# Adafruit_nRF52840_Bluefruit_Feather_Expr.net
KiCad netlist of a schematic drawn in EAGLE
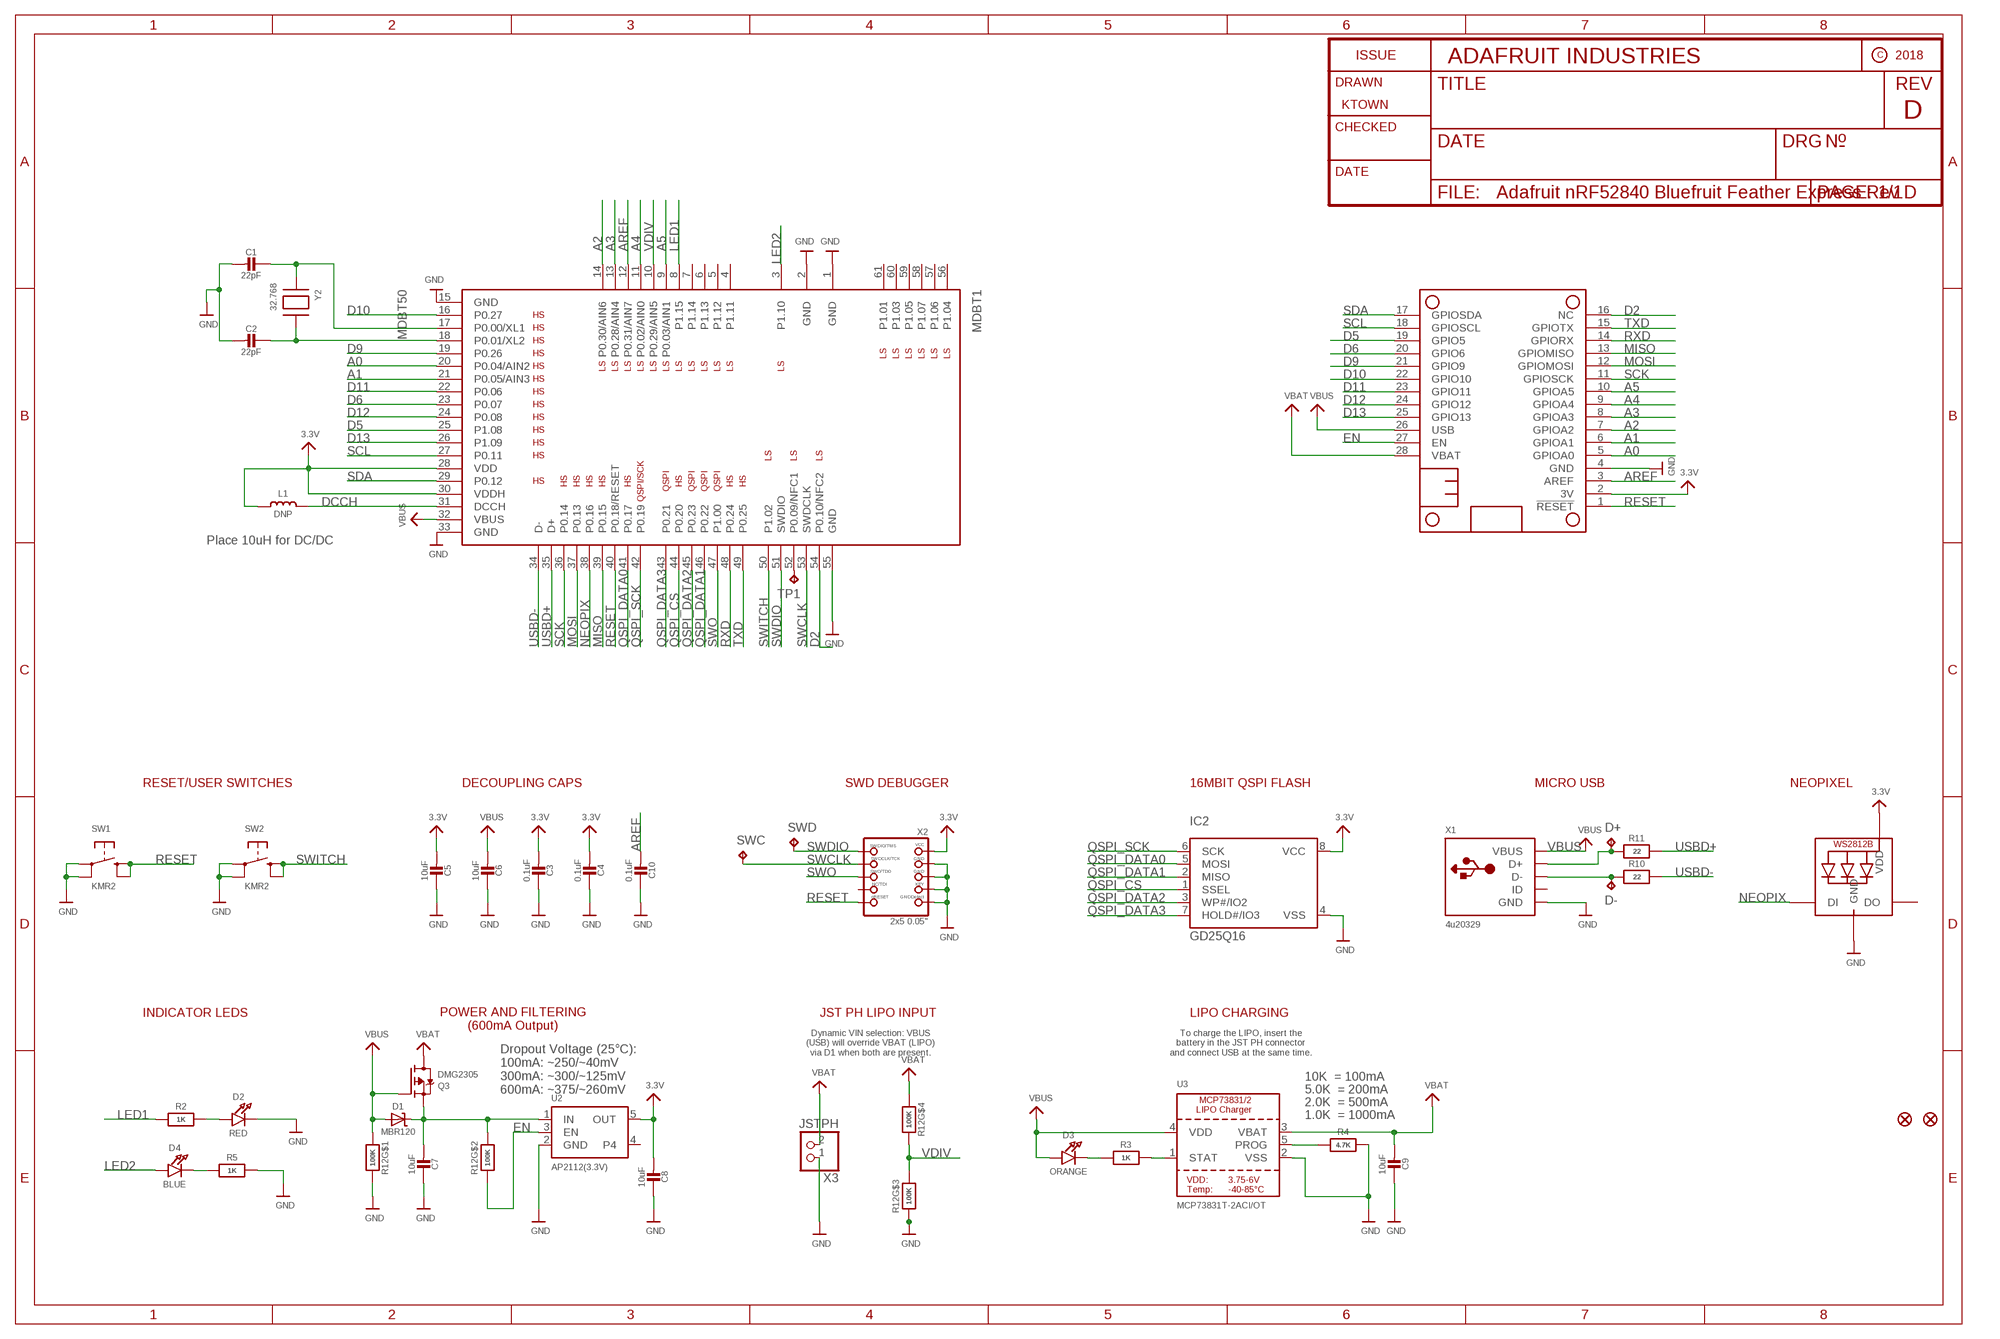
[diagram p0: schematic, sheet 1]

(export (version "E")
  (design (tool "Eeschema 10.0.6"))
  (components
    (comp (ref "C1")
      (value "22pF")
      (footprint "eagle-import:0603-NO")
      (libsource (lib "eagle-import") (part "CAP_CERAMIC0603_NO"))
    )
    (comp (ref "C2")
      (value "22pF")
      (footprint "eagle-import:0603-NO")
      (libsource (lib "eagle-import") (part "CAP_CERAMIC0603_NO"))
    )
    (comp (ref "C3")
      (value "0.1uF")
      (footprint "eagle-import:0603-NO")
      (libsource (lib "eagle-import") (part "CAP_CERAMIC0603_NO"))
    )
    (comp (ref "C4")
      (value "0.1uF")
      (footprint "eagle-import:0603-NO")
      (libsource (lib "eagle-import") (part "CAP_CERAMIC0603_NO"))
    )
    (comp (ref "C5")
      (value "10uF")
      (footprint "eagle-import:0805-NO")
      (libsource (lib "eagle-import") (part "CAP_CERAMIC0805-NOOUTLINE"))
    )
    (comp (ref "C6")
      (value "10uF")
      (footprint "eagle-import:0805-NO")
      (libsource (lib "eagle-import") (part "CAP_CERAMIC0805-NOOUTLINE"))
    )
    (comp (ref "C7")
      (value "10uF")
      (footprint "eagle-import:0805-NO")
      (libsource (lib "eagle-import") (part "CAP_CERAMIC0805-NOOUTLINE"))
    )
    (comp (ref "C8")
      (value "10uF")
      (footprint "eagle-import:0805-NO")
      (libsource (lib "eagle-import") (part "CAP_CERAMIC0805-NOOUTLINE"))
    )
    (comp (ref "C9")
      (value "10uF")
      (footprint "eagle-import:0805-NO")
      (libsource (lib "eagle-import") (part "CAP_CERAMIC0805-NOOUTLINE"))
    )
    (comp (ref "C10")
      (value "0.1uF")
      (footprint "eagle-import:0603-NO")
      (libsource (lib "eagle-import") (part "CAP_CERAMIC0603_NO"))
    )
    (comp (ref "D+")
      (value "TPTP10R")
      (footprint "eagle-import:TP10R")
      (libsource (lib "eagle-import") (part "TPTP10R"))
    )
    (comp (ref "D-")
      (value "TPTP10R")
      (footprint "eagle-import:TP10R")
      (libsource (lib "eagle-import") (part "TPTP10R"))
    )
    (comp (ref "D1")
      (value "MBR120")
      (footprint "eagle-import:SOD-123")
      (libsource (lib "eagle-import") (part "DIODE-SCHOTTKYSOD-123"))
    )
    (comp (ref "D2")
      (value "RED")
      (footprint "eagle-import:CHIPLED_0805_NOOUTLINE")
      (libsource (lib "eagle-import") (part "LED0805_NOOUTLINE"))
    )
    (comp (ref "D3")
      (value "ORANGE")
      (footprint "eagle-import:CHIPLED_0805_NOOUTLINE")
      (libsource (lib "eagle-import") (part "LED0805_NOOUTLINE"))
    )
    (comp (ref "D4")
      (value "BLUE")
      (footprint "eagle-import:CHIPLED_0805_NOOUTLINE")
      (libsource (lib "eagle-import") (part "LED0805_NOOUTLINE"))
    )
    (comp (ref "FID1")
      (value "FIDUCIAL_1MM")
      (footprint "eagle-import:FIDUCIAL_1MM")
      (libsource (lib "eagle-import") (part "FIDUCIAL_1MM"))
    )
    (comp (ref "FID2")
      (value "FIDUCIAL_1MM")
      (footprint "eagle-import:FIDUCIAL_1MM")
      (libsource (lib "eagle-import") (part "FIDUCIAL_1MM"))
    )
    (comp (ref "IC2")
      (value "GD25Q16")
      (footprint "eagle-import:USON8")
      (libsource (lib "eagle-import") (part "SPIFLASH_8PINUX"))
    )
    (comp (ref "L1")
      (value "DNP")
      (footprint "eagle-import:_0805MP")
      (libsource (lib "eagle-import") (part "INDUCTOR_0805MP"))
    )
    (comp (ref "LED1")
      (value "WS2812B3535")
      (footprint "eagle-import:LED3535")
      (libsource (lib "eagle-import") (part "WS2812B3535"))
    )
    (comp (ref "MDBT1")
      (value "MDBT50")
      (footprint "eagle-import:MDBT50")
      (libsource (lib "eagle-import") (part "MDBT50"))
    )
    (comp (ref "MS1")
      (value "FEATHERWING_NODIM")
      (footprint "eagle-import:FEATHERWING_NODIM")
      (libsource (lib "eagle-import") (part "FEATHERWING_NODIM"))
    )
    (comp (ref "Q3")
      (value "DMG2305")
      (footprint "eagle-import:SOT23-R")
      (libsource (lib "eagle-import") (part "MOSFET-P"))
    )
    (comp (ref "R2")
      (value "1K")
      (footprint "eagle-import:0603-NO")
      (libsource (lib "eagle-import") (part "RESISTOR_0603_NOOUT"))
    )
    (comp (ref "R3")
      (value "1K")
      (footprint "eagle-import:0603-NO")
      (libsource (lib "eagle-import") (part "RESISTOR_0603_NOOUT"))
    )
    (comp (ref "R4")
      (value "4.7K")
      (footprint "eagle-import:0603-NO")
      (libsource (lib "eagle-import") (part "RESISTOR_0603_NOOUT"))
    )
    (comp (ref "R5")
      (value "1K")
      (footprint "eagle-import:0603-NO")
      (libsource (lib "eagle-import") (part "RESISTOR_0603_NOOUT"))
    )
    (comp (ref "R10")
      (value "22")
      (footprint "eagle-import:0603-NO")
      (libsource (lib "eagle-import") (part "RESISTOR_0603_NOOUT"))
    )
    (comp (ref "R11")
      (value "22")
      (footprint "eagle-import:0603-NO")
      (libsource (lib "eagle-import") (part "RESISTOR_0603_NOOUT"))
    )
    (comp (ref "R12")
      (value "100K")
      (footprint "eagle-import:RESPACK_4X0603")
      (libsource (lib "eagle-import") (part "RESISTOR_4PACK"))
    )
    (comp (ref "SW1")
      (value "KMR2")
      (footprint "eagle-import:BTN_KMR2_4.6X2.8")
      (libsource (lib "eagle-import") (part "SWITCH_TACT_SMT4.6X2.8"))
    )
    (comp (ref "SW2")
      (value "KMR2")
      (footprint "eagle-import:BTN_KMR2_4.6X2.8")
      (libsource (lib "eagle-import") (part "SWITCH_TACT_SMT4.6X2.8"))
    )
    (comp (ref "SWC")
      (value "TPTP12R")
      (footprint "eagle-import:TP12R")
      (libsource (lib "eagle-import") (part "TPTP12R"))
    )
    (comp (ref "SWD")
      (value "TPTP12R")
      (footprint "eagle-import:TP12R")
      (libsource (lib "eagle-import") (part "TPTP12R"))
    )
    (comp (ref "TP1")
      (value "TPTP10R")
      (footprint "eagle-import:TP10R")
      (libsource (lib "eagle-import") (part "TPTP10R"))
    )
    (comp (ref "U2")
      (value "AP2112(3.3V)")
      (footprint "eagle-import:SOT23-5")
      (libsource (lib "eagle-import") (part "VREG_SOT23-5"))
    )
    (comp (ref "U3")
      (value "MCP73831T-2ACI/OT")
      (footprint "eagle-import:SOT23-5")
      (libsource (lib "eagle-import") (part "MCP73831/2"))
    )
    (comp (ref "X1")
      (value "4u20329")
      (footprint "eagle-import:4UCONN_20329_V2")
      (libsource (lib "eagle-import") (part "USB_MICRO_20329_V2"))
    )
    (comp (ref "X2")
      (value "2x5 0.05\"")
      (footprint "eagle-import:2X05_1.27MM_BOX_POSTS")
      (libsource (lib "eagle-import") (part "JTAG-CORTEXBOXPOSTS"))
    )
    (comp (ref "X3")
      (value "JSTPH")
      (footprint "eagle-import:JSTPH2")
      (libsource (lib "eagle-import") (part "CON_JST_PH_2PIN"))
    )
    (comp (ref "Y2")
      (value "32.768")
      (footprint "eagle-import:XTAL3215")
      (libsource (lib "eagle-import") (part "XTAL-3.2X1.5"))
    )
  )
  (nets
    (net (code "1") (name "/A0") (class "Default")
      (node (ref "MDBT1") (pin "20") (pinfunction "P0.04/AIN2_20") (pintype "bidirectional"))
      (node (ref "MS1") (pin "5") (pinfunction "GPIOA0_5") (pintype "bidirectional"))
    )
    (net (code "2") (name "/A1") (class "Default")
      (node (ref "MDBT1") (pin "21") (pinfunction "P0.05/AIN3_21") (pintype "bidirectional"))
      (node (ref "MS1") (pin "6") (pinfunction "GPIOA1_6") (pintype "bidirectional"))
    )
    (net (code "3") (name "/A2") (class "Default")
      (node (ref "MDBT1") (pin "14") (pinfunction "P0.30/AIN6_14") (pintype "bidirectional"))
      (node (ref "MS1") (pin "7") (pinfunction "GPIOA2_7") (pintype "bidirectional"))
    )
    (net (code "4") (name "/A3") (class "Default")
      (node (ref "MDBT1") (pin "13") (pinfunction "P0.28/AIN4_13") (pintype "bidirectional"))
      (node (ref "MS1") (pin "8") (pinfunction "GPIOA3_8") (pintype "bidirectional"))
    )
    (net (code "5") (name "/A4") (class "Default")
      (node (ref "MDBT1") (pin "11") (pinfunction "P0.02/AIN0_11") (pintype "bidirectional"))
      (node (ref "MS1") (pin "9") (pinfunction "GPIOA4_9") (pintype "bidirectional"))
    )
    (net (code "6") (name "/A5") (class "Default")
      (node (ref "MDBT1") (pin "9") (pinfunction "P0.03/AIN1_9") (pintype "bidirectional"))
      (node (ref "MS1") (pin "10") (pinfunction "GPIOA5_10") (pintype "bidirectional"))
    )
    (net (code "7") (name "/AREF") (class "Default")
      (node (ref "C10") (pin "2") (pinfunction "2_2") (pintype "passive"))
      (node (ref "MDBT1") (pin "12") (pinfunction "P0.31/AIN7_12") (pintype "bidirectional"))
      (node (ref "MS1") (pin "3") (pinfunction "AREF_3") (pintype "passive"))
    )
    (net (code "8") (name "/D2") (class "Default")
      (node (ref "MDBT1") (pin "54") (pinfunction "P0.10/NFC2_54") (pintype "bidirectional"))
      (node (ref "MS1") (pin "16") (pinfunction "NC_16") (pintype "passive"))
    )
    (net (code "9") (name "/D5") (class "Default")
      (node (ref "MDBT1") (pin "25") (pinfunction "P1.08_25") (pintype "bidirectional"))
      (node (ref "MS1") (pin "19") (pinfunction "GPIO5_19") (pintype "bidirectional"))
    )
    (net (code "10") (name "/D6") (class "Default")
      (node (ref "MDBT1") (pin "23") (pinfunction "P0.07_23") (pintype "bidirectional"))
      (node (ref "MS1") (pin "20") (pinfunction "GPIO6_20") (pintype "bidirectional"))
    )
    (net (code "11") (name "/D9") (class "Default")
      (node (ref "MDBT1") (pin "19") (pinfunction "P0.26_19") (pintype "bidirectional"))
      (node (ref "MS1") (pin "21") (pinfunction "GPIO9_21") (pintype "bidirectional"))
    )
    (net (code "12") (name "/D10") (class "Default")
      (node (ref "MDBT1") (pin "16") (pinfunction "P0.27_16") (pintype "bidirectional"))
      (node (ref "MS1") (pin "22") (pinfunction "GPIO10_22") (pintype "bidirectional"))
    )
    (net (code "13") (name "/D11") (class "Default")
      (node (ref "MDBT1") (pin "22") (pinfunction "P0.06_22") (pintype "bidirectional"))
      (node (ref "MS1") (pin "23") (pinfunction "GPIO11_23") (pintype "bidirectional"))
    )
    (net (code "14") (name "/D12") (class "Default")
      (node (ref "MDBT1") (pin "24") (pinfunction "P0.08_24") (pintype "bidirectional"))
      (node (ref "MS1") (pin "24") (pinfunction "GPIO12_24") (pintype "bidirectional"))
    )
    (net (code "15") (name "/D13") (class "Default")
      (node (ref "MDBT1") (pin "26") (pinfunction "P1.09_26") (pintype "bidirectional"))
      (node (ref "MS1") (pin "25") (pinfunction "GPIO13_25") (pintype "bidirectional"))
    )
    (net (code "16") (name "/DCCH") (class "Default")
      (node (ref "L1") (pin "2") (pinfunction "2_2") (pintype "passive"))
      (node (ref "MDBT1") (pin "31") (pinfunction "DCCH_31") (pintype "bidirectional"))
    )
    (net (code "17") (name "/EN") (class "Default")
      (node (ref "MS1") (pin "27") (pinfunction "EN_27") (pintype "passive"))
      (node (ref "R12") (pin "2") (pinfunction "1_2") (pintype "passive"))
      (node (ref "U2") (pin "3") (pinfunction "EN_3") (pintype "input"))
    )
    (net (code "18") (name "/LED1") (class "Default")
      (node (ref "MDBT1") (pin "8") (pinfunction "P1.15_8") (pintype "bidirectional"))
      (node (ref "R2") (pin "1") (pinfunction "1_1") (pintype "passive"))
    )
    (net (code "19") (name "/LED2") (class "Default")
      (node (ref "D4") (pin "A") (pinfunction "A_A") (pintype "passive"))
      (node (ref "MDBT1") (pin "3") (pinfunction "P1.10_3") (pintype "bidirectional"))
    )
    (net (code "20") (name "/MISO") (class "Default")
      (node (ref "MDBT1") (pin "39") (pinfunction "P0.15_39") (pintype "bidirectional"))
      (node (ref "MS1") (pin "13") (pinfunction "GPIOMISO_13") (pintype "bidirectional"))
    )
    (net (code "21") (name "/MOSI") (class "Default")
      (node (ref "MDBT1") (pin "37") (pinfunction "P0.13_37") (pintype "bidirectional"))
      (node (ref "MS1") (pin "12") (pinfunction "GPIOMOSI_12") (pintype "bidirectional"))
    )
    (net (code "22") (name "/NEOPIX") (class "Default")
      (node (ref "LED1") (pin "1") (pinfunction "DI_1") (pintype "input"))
      (node (ref "MDBT1") (pin "38") (pinfunction "P0.16_38") (pintype "bidirectional"))
    )
    (net (code "23") (name "/QSPI_CS") (class "Default")
      (node (ref "IC2") (pin "1") (pinfunction "SSEL_1") (pintype "bidirectional"))
      (node (ref "MDBT1") (pin "44") (pinfunction "P0.20_44") (pintype "bidirectional"))
    )
    (net (code "24") (name "/QSPI_DATA0") (class "Default")
      (node (ref "IC2") (pin "5") (pinfunction "MOSI_5") (pintype "bidirectional"))
      (node (ref "MDBT1") (pin "41") (pinfunction "P0.17_41") (pintype "bidirectional"))
    )
    (net (code "25") (name "/QSPI_DATA1") (class "Default")
      (node (ref "IC2") (pin "2") (pinfunction "MISO_2") (pintype "bidirectional"))
      (node (ref "MDBT1") (pin "46") (pinfunction "P0.22_46") (pintype "bidirectional"))
    )
    (net (code "26") (name "/QSPI_DATA2") (class "Default")
      (node (ref "IC2") (pin "3") (pinfunction "WP#/IO2_3") (pintype "bidirectional"))
      (node (ref "MDBT1") (pin "45") (pinfunction "P0.23_45") (pintype "bidirectional"))
    )
    (net (code "27") (name "/QSPI_DATA3") (class "Default")
      (node (ref "IC2") (pin "7") (pinfunction "HOLD#/IO3_7") (pintype "bidirectional"))
      (node (ref "MDBT1") (pin "43") (pinfunction "P0.21_43") (pintype "bidirectional"))
    )
    (net (code "28") (name "/QSPI_SCK") (class "Default")
      (node (ref "IC2") (pin "6") (pinfunction "SCK_6") (pintype "bidirectional"))
      (node (ref "MDBT1") (pin "42") (pinfunction "P0.19_42") (pintype "bidirectional"))
    )
    (net (code "29") (name "/RESET") (class "Default")
      (node (ref "MDBT1") (pin "40") (pinfunction "P0.18/RESET_40") (pintype "bidirectional"))
      (node (ref "MS1") (pin "1") (pinfunction "~{RESET}_1") (pintype "input"))
      (node (ref "SW1") (pin "B") (pinfunction "S_B") (pintype "passive"))
      (node (ref "SW1") (pin "B'") (pinfunction "S1_B'") (pintype "passive"))
      (node (ref "X2") (pin "10") (pinfunction "NRESET_10") (pintype "bidirectional"))
    )
    (net (code "30") (name "/RXD") (class "Default")
      (node (ref "MDBT1") (pin "48") (pinfunction "P0.24_48") (pintype "bidirectional"))
      (node (ref "MS1") (pin "14") (pinfunction "GPIORX_14") (pintype "bidirectional"))
    )
    (net (code "31") (name "/SCK") (class "Default")
      (node (ref "MDBT1") (pin "36") (pinfunction "P0.14_36") (pintype "bidirectional"))
      (node (ref "MS1") (pin "11") (pinfunction "GPIOSCK_11") (pintype "bidirectional"))
    )
    (net (code "32") (name "/SCL") (class "Default")
      (node (ref "MDBT1") (pin "27") (pinfunction "P0.11_27") (pintype "bidirectional"))
      (node (ref "MS1") (pin "18") (pinfunction "GPIOSCL_18") (pintype "bidirectional"))
    )
    (net (code "33") (name "/SDA") (class "Default")
      (node (ref "MDBT1") (pin "29") (pinfunction "P0.12_29") (pintype "bidirectional"))
      (node (ref "MS1") (pin "17") (pinfunction "GPIOSDA_17") (pintype "bidirectional"))
    )
    (net (code "34") (name "/SWCLK") (class "Default")
      (node (ref "MDBT1") (pin "53") (pinfunction "SWDCLK_53") (pintype "bidirectional"))
      (node (ref "SWC") (pin "TP") (pinfunction "TP_TP") (pintype "input"))
      (node (ref "X2") (pin "4") (pinfunction "SWDCLK_4") (pintype "bidirectional"))
    )
    (net (code "35") (name "/SWDIO") (class "Default")
      (node (ref "MDBT1") (pin "51") (pinfunction "SWDIO_51") (pintype "bidirectional"))
      (node (ref "SWD") (pin "TP") (pinfunction "TP_TP") (pintype "input"))
      (node (ref "X2") (pin "2") (pinfunction "SWDIO_2") (pintype "bidirectional"))
    )
    (net (code "36") (name "/SWITCH") (class "Default")
      (node (ref "MDBT1") (pin "50") (pinfunction "P1.02_50") (pintype "bidirectional"))
      (node (ref "SW2") (pin "B") (pinfunction "S_B") (pintype "passive"))
      (node (ref "SW2") (pin "B'") (pinfunction "S1_B'") (pintype "passive"))
    )
    (net (code "37") (name "/SWO") (class "Default")
      (node (ref "MDBT1") (pin "47") (pinfunction "P1.00_47") (pintype "bidirectional"))
      (node (ref "X2") (pin "6") (pinfunction "SWO_6") (pintype "bidirectional"))
    )
    (net (code "38") (name "/TXD") (class "Default")
      (node (ref "MDBT1") (pin "49") (pinfunction "P0.25_49") (pintype "bidirectional"))
      (node (ref "MS1") (pin "15") (pinfunction "GPIOTX_15") (pintype "bidirectional"))
    )
    (net (code "39") (name "/USBD+") (class "Default")
      (node (ref "MDBT1") (pin "35") (pinfunction "D+_35") (pintype "bidirectional"))
      (node (ref "R11") (pin "2") (pinfunction "2_2") (pintype "passive"))
    )
    (net (code "40") (name "/USBD-") (class "Default")
      (node (ref "MDBT1") (pin "34") (pinfunction "D-_34") (pintype "bidirectional"))
      (node (ref "R10") (pin "2") (pinfunction "2_2") (pintype "passive"))
    )
    (net (code "41") (name "/VDIV") (class "Default")
      (node (ref "MDBT1") (pin "10") (pinfunction "P0.29/AIN5_10") (pintype "bidirectional"))
      (node (ref "R12") (pin "5") (pinfunction "2_5") (pintype "passive"))
      (node (ref "R12") (pin "6") (pinfunction "2_6") (pintype "passive"))
    )
    (net (code "42") (name "3.3V") (class "Default")
      (node (ref "C3") (pin "2") (pinfunction "2_2") (pintype "passive"))
      (node (ref "C4") (pin "2") (pinfunction "2_2") (pintype "passive"))
      (node (ref "C5") (pin "2") (pinfunction "2_2") (pintype "passive"))
      (node (ref "C8") (pin "2") (pinfunction "2_2") (pintype "passive"))
      (node (ref "IC2") (pin "8") (pinfunction "VCC_8") (pintype "bidirectional"))
      (node (ref "L1") (pin "1") (pinfunction "1_1") (pintype "passive"))
      (node (ref "LED1") (pin "2") (pinfunction "VDD_2") (pintype "power_in"))
      (node (ref "MDBT1") (pin "28") (pinfunction "VDD_28") (pintype "bidirectional"))
      (node (ref "MDBT1") (pin "30") (pinfunction "VDDH_30") (pintype "bidirectional"))
      (node (ref "MS1") (pin "2") (pinfunction "3V_2") (pintype "power_in"))
      (node (ref "U2") (pin "5") (pinfunction "OUT_5") (pintype "power_in"))
      (node (ref "X2") (pin "1") (pinfunction "VCC_1") (pintype "power_in"))
    )
    (net (code "43") (name "GND") (class "Default")
      (node (ref "C1") (pin "2") (pinfunction "2_2") (pintype "passive"))
      (node (ref "C10") (pin "1") (pinfunction "1_1") (pintype "passive"))
      (node (ref "C2") (pin "2") (pinfunction "2_2") (pintype "passive"))
      (node (ref "C3") (pin "1") (pinfunction "1_1") (pintype "passive"))
      (node (ref "C4") (pin "1") (pinfunction "1_1") (pintype "passive"))
      (node (ref "C5") (pin "1") (pinfunction "1_1") (pintype "passive"))
      (node (ref "C6") (pin "1") (pinfunction "1_1") (pintype "passive"))
      (node (ref "C7") (pin "1") (pinfunction "1_1") (pintype "passive"))
      (node (ref "C8") (pin "1") (pinfunction "1_1") (pintype "passive"))
      (node (ref "C9") (pin "1") (pinfunction "1_1") (pintype "passive"))
      (node (ref "D2") (pin "C") (pinfunction "C_C") (pintype "passive"))
      (node (ref "IC2") (pin "4") (pinfunction "VSS_4") (pintype "bidirectional"))
      (node (ref "LED1") (pin "4") (pinfunction "GND_4") (pintype "power_in"))
      (node (ref "MDBT1") (pin "1") (pinfunction "GND_1") (pintype "bidirectional"))
      (node (ref "MDBT1") (pin "15") (pinfunction "GND_15") (pintype "bidirectional"))
      (node (ref "MDBT1") (pin "2") (pinfunction "GND_2") (pintype "bidirectional"))
      (node (ref "MDBT1") (pin "33") (pinfunction "GND_33") (pintype "bidirectional"))
      (node (ref "MDBT1") (pin "55") (pinfunction "GND_55") (pintype "bidirectional"))
      (node (ref "MS1") (pin "4") (pinfunction "GND_4") (pintype "power_in"))
      (node (ref "R12") (pin "3") (pinfunction "1_3") (pintype "passive"))
      (node (ref "R12") (pin "8") (pinfunction "2_8") (pintype "passive"))
      (node (ref "R4") (pin "2") (pinfunction "2_2") (pintype "passive"))
      (node (ref "R5") (pin "2") (pinfunction "2_2") (pintype "passive"))
      (node (ref "SW1") (pin "A") (pinfunction "P_A") (pintype "passive"))
      (node (ref "SW1") (pin "A'") (pinfunction "P1_A'") (pintype "passive"))
      (node (ref "SW2") (pin "A") (pinfunction "P_A") (pintype "passive"))
      (node (ref "SW2") (pin "A'") (pinfunction "P1_A'") (pintype "passive"))
      (node (ref "U2") (pin "2") (pinfunction "GND_2") (pintype "power_in"))
      (node (ref "U3") (pin "2") (pinfunction "VSS_2") (pintype "power_in"))
      (node (ref "X1") (pin "BASE@1") (pinfunction "GND_BASE@1") (pintype "power_in"))
      (node (ref "X1") (pin "BASE@2") (pinfunction "GND_BASE@2") (pintype "power_in"))
      (node (ref "X1") (pin "GND") (pinfunction "GND_GND") (pintype "power_in"))
      (node (ref "X1") (pin "SPRT@1") (pinfunction "GND_SPRT@1") (pintype "power_in"))
      (node (ref "X1") (pin "SPRT@2") (pinfunction "GND_SPRT@2") (pintype "power_in"))
      (node (ref "X1") (pin "SPRT@3") (pinfunction "GND_SPRT@3") (pintype "power_in"))
      (node (ref "X1") (pin "SPRT@4") (pinfunction "GND_SPRT@4") (pintype "power_in"))
      (node (ref "X2") (pin "3") (pinfunction "GND_3") (pintype "power_in"))
      (node (ref "X2") (pin "5") (pinfunction "GND_5") (pintype "power_in"))
      (node (ref "X2") (pin "7") (pinfunction "KEY_7") (pintype "bidirectional"))
      (node (ref "X2") (pin "9") (pinfunction "GNDDETECT_9") (pintype "bidirectional"))
      (node (ref "X3") (pin "1") (pinfunction "1_1") (pintype "passive"))
    )
    (net (code "44") (name "Net-(D+-PadTP)") (class "Default")
      (node (ref "D+") (pin "TP") (pinfunction "TP_TP") (pintype "input"))
      (node (ref "R11") (pin "1") (pinfunction "1_1") (pintype "passive"))
      (node (ref "X1") (pin "D+") (pinfunction "D+_D+") (pintype "bidirectional"))
    )
    (net (code "45") (name "Net-(D--PadTP)") (class "Default")
      (node (ref "D-") (pin "TP") (pinfunction "TP_TP") (pintype "input"))
      (node (ref "R10") (pin "1") (pinfunction "1_1") (pintype "passive"))
      (node (ref "X1") (pin "D-") (pinfunction "D-_D-") (pintype "bidirectional"))
    )
    (net (code "46") (name "Net-(D2-PadA)") (class "Default")
      (node (ref "D2") (pin "A") (pinfunction "A_A") (pintype "passive"))
      (node (ref "R2") (pin "2") (pinfunction "2_2") (pintype "passive"))
    )
    (net (code "47") (name "Net-(D3-PadC)") (class "Default")
      (node (ref "D3") (pin "C") (pinfunction "C_C") (pintype "passive"))
      (node (ref "R3") (pin "1") (pinfunction "1_1") (pintype "passive"))
    )
    (net (code "48") (name "Net-(D4-PadC)") (class "Default")
      (node (ref "D4") (pin "C") (pinfunction "C_C") (pintype "passive"))
      (node (ref "R5") (pin "1") (pinfunction "1_1") (pintype "passive"))
    )
    (net (code "49") (name "Net-(MDBT1-P0.00{slash}XL1)") (class "Default")
      (node (ref "C1") (pin "1") (pinfunction "1_1") (pintype "passive"))
      (node (ref "MDBT1") (pin "17") (pinfunction "P0.00/XL1_17") (pintype "bidirectional"))
      (node (ref "Y2") (pin "P$1") (pinfunction "P$1_P$1") (pintype "bidirectional"))
    )
    (net (code "50") (name "Net-(MDBT1-P0.01{slash}XL2)") (class "Default")
      (node (ref "C2") (pin "1") (pinfunction "1_1") (pintype "passive"))
      (node (ref "MDBT1") (pin "18") (pinfunction "P0.01/XL2_18") (pintype "bidirectional"))
      (node (ref "Y2") (pin "P$2") (pinfunction "P$2_P$2") (pintype "bidirectional"))
    )
    (net (code "51") (name "Net-(MDBT1-P0.09{slash}NFC1)") (class "Default")
      (node (ref "MDBT1") (pin "52") (pinfunction "P0.09/NFC1_52") (pintype "bidirectional"))
      (node (ref "TP1") (pin "TP") (pinfunction "TP_TP") (pintype "input"))
    )
    (net (code "52") (name "Net-(Q3-S)") (class "Default")
      (node (ref "C7") (pin "2") (pinfunction "2_2") (pintype "passive"))
      (node (ref "D1") (pin "C") (pinfunction "C_C") (pintype "passive"))
      (node (ref "Q3") (pin "2") (pinfunction "S_2") (pintype "passive"))
      (node (ref "R12") (pin "7") (pinfunction "2_7") (pintype "passive"))
      (node (ref "U2") (pin "1") (pinfunction "IN_1") (pintype "power_in"))
    )
    (net (code "53") (name "Net-(U3-PROG)") (class "Default")
      (node (ref "R4") (pin "1") (pinfunction "1_1") (pintype "passive"))
      (node (ref "U3") (pin "5") (pinfunction "PROG_5") (pintype "input"))
    )
    (net (code "54") (name "Net-(U3-STAT)") (class "Default")
      (node (ref "R3") (pin "2") (pinfunction "2_2") (pintype "passive"))
      (node (ref "U3") (pin "1") (pinfunction "STAT_1") (pintype "output"))
    )
    (net (code "55") (name "VBAT") (class "Default")
      (node (ref "C9") (pin "2") (pinfunction "2_2") (pintype "passive"))
      (node (ref "MS1") (pin "28") (pinfunction "VBAT_28") (pintype "power_in"))
      (node (ref "Q3") (pin "3") (pinfunction "D_3") (pintype "passive"))
      (node (ref "R12") (pin "4") (pinfunction "1_4") (pintype "passive"))
      (node (ref "U3") (pin "3") (pinfunction "VBAT_3") (pintype "power_in"))
      (node (ref "X3") (pin "2") (pinfunction "2_2") (pintype "passive"))
    )
    (net (code "56") (name "VBUS") (class "Default")
      (node (ref "C6") (pin "2") (pinfunction "2_2") (pintype "passive"))
      (node (ref "D1") (pin "A") (pinfunction "A_A") (pintype "passive"))
      (node (ref "D3") (pin "A") (pinfunction "A_A") (pintype "passive"))
      (node (ref "MDBT1") (pin "32") (pinfunction "VBUS_32") (pintype "bidirectional"))
      (node (ref "MS1") (pin "26") (pinfunction "USB_26") (pintype "power_in"))
      (node (ref "Q3") (pin "1") (pinfunction "G_1") (pintype "passive"))
      (node (ref "R12") (pin "1") (pinfunction "1_1") (pintype "passive"))
      (node (ref "U3") (pin "4") (pinfunction "VDD_4") (pintype "power_in"))
      (node (ref "X1") (pin "VBUS") (pinfunction "VBUS_VBUS") (pintype "power_in"))
    )
    (net (code "57") (name "unconnected-(LED1-DO-Pad3)") (class "Default")
      (node (ref "LED1") (pin "3") (pinfunction "DO_3") (pintype "output"))
    )
    (net (code "58") (name "unconnected-(MDBT1-P1.01-Pad61)") (class "Default")
      (node (ref "MDBT1") (pin "61") (pinfunction "P1.01_61") (pintype "bidirectional"))
    )
    (net (code "59") (name "unconnected-(MDBT1-P1.03-Pad60)") (class "Default")
      (node (ref "MDBT1") (pin "60") (pinfunction "P1.03_60") (pintype "bidirectional"))
    )
    (net (code "60") (name "unconnected-(MDBT1-P1.04-Pad56)") (class "Default")
      (node (ref "MDBT1") (pin "56") (pinfunction "P1.04_56") (pintype "bidirectional"))
    )
    (net (code "61") (name "unconnected-(MDBT1-P1.05-Pad59)") (class "Default")
      (node (ref "MDBT1") (pin "59") (pinfunction "P1.05_59") (pintype "bidirectional"))
    )
    (net (code "62") (name "unconnected-(MDBT1-P1.06-Pad57)") (class "Default")
      (node (ref "MDBT1") (pin "57") (pinfunction "P1.06_57") (pintype "bidirectional"))
    )
    (net (code "63") (name "unconnected-(MDBT1-P1.07-Pad58)") (class "Default")
      (node (ref "MDBT1") (pin "58") (pinfunction "P1.07_58") (pintype "bidirectional"))
    )
    (net (code "64") (name "unconnected-(MDBT1-P1.11-Pad4)") (class "Default")
      (node (ref "MDBT1") (pin "4") (pinfunction "P1.11_4") (pintype "bidirectional"))
    )
    (net (code "65") (name "unconnected-(MDBT1-P1.12-Pad5)") (class "Default")
      (node (ref "MDBT1") (pin "5") (pinfunction "P1.12_5") (pintype "bidirectional"))
    )
    (net (code "66") (name "unconnected-(MDBT1-P1.13-Pad6)") (class "Default")
      (node (ref "MDBT1") (pin "6") (pinfunction "P1.13_6") (pintype "bidirectional"))
    )
    (net (code "67") (name "unconnected-(MDBT1-P1.14-Pad7)") (class "Default")
      (node (ref "MDBT1") (pin "7") (pinfunction "P1.14_7") (pintype "bidirectional"))
    )
    (net (code "68") (name "unconnected-(U2-P4-Pad4)") (class "Default")
      (node (ref "U2") (pin "4") (pinfunction "P4_4") (pintype "bidirectional"))
    )
    (net (code "69") (name "unconnected-(X1-PadID)") (class "Default")
      (node (ref "X1") (pin "ID") (pinfunction "ID_ID") (pintype "bidirectional"))
    )
    (net (code "70") (name "unconnected-(X2-TDI-Pad8)") (class "Default")
      (node (ref "X2") (pin "8") (pinfunction "TDI_8") (pintype "bidirectional"))
    )
  )
)
